# interposer.net
KiCad netlist of a schematic drawn in Altium Designer
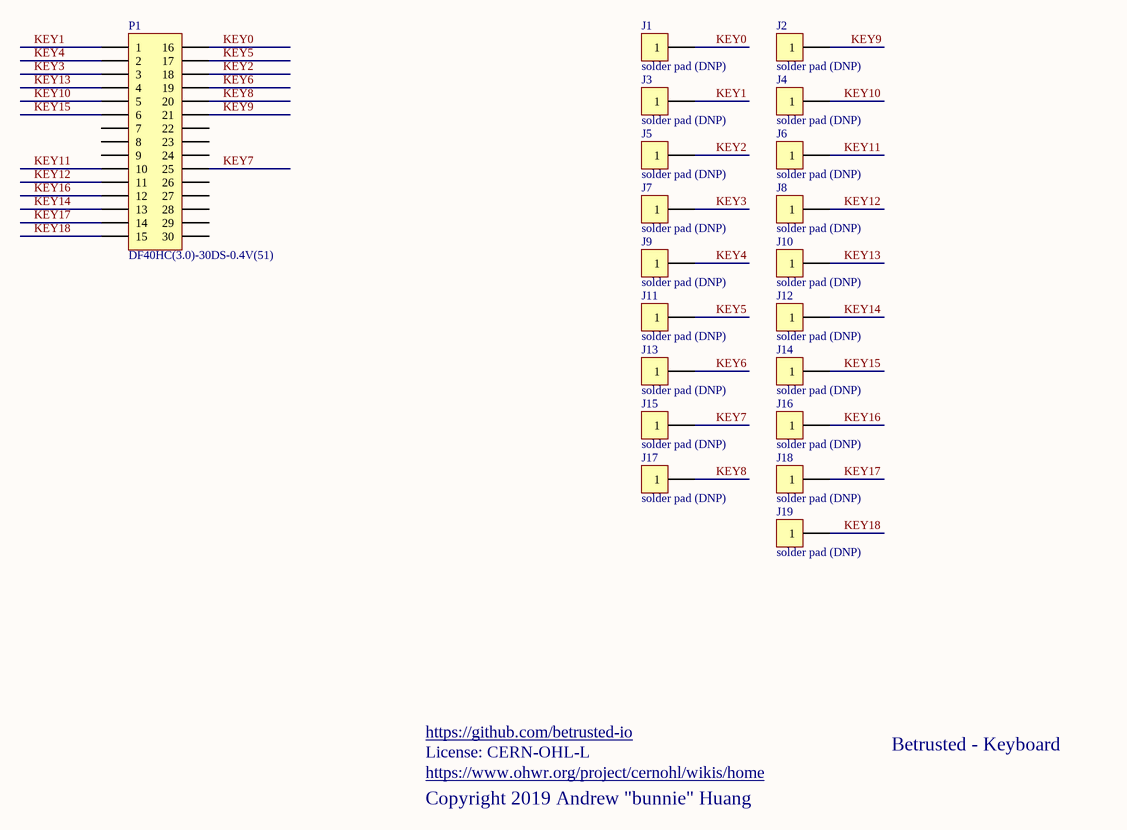
[diagram p0: interposer.SchDoc]

(export (version "E")
  (design (tool "Eeschema 10.0.6"))
  (components
    (comp (ref "J1")
      (value "solder pad (DNP)")
      (footprint "TP_TH1.0mm_1.5x2mm_SQ")
      (description "Connector")
      (fields (field (name "MPN") "DNP"))
      (libsource (lib "*") (part "CON1"))
    )
    (comp (ref "J2")
      (value "solder pad (DNP)")
      (footprint "TP_TH1.0mm_1.5x2mm_SQ")
      (description "Connector")
      (fields (field (name "MPN") "DNP"))
      (libsource (lib "*") (part "CON1"))
    )
    (comp (ref "J3")
      (value "solder pad (DNP)")
      (footprint "TP_TH1.0mm_1.5x2mm_SQ")
      (description "Connector")
      (fields (field (name "MPN") "DNP"))
      (libsource (lib "*") (part "CON1"))
    )
    (comp (ref "J4")
      (value "solder pad (DNP)")
      (footprint "TP_TH1.0mm_1.5x2mm_SQ")
      (description "Connector")
      (fields (field (name "MPN") "DNP"))
      (libsource (lib "*") (part "CON1"))
    )
    (comp (ref "J5")
      (value "solder pad (DNP)")
      (footprint "TP_TH1.0mm_1.5x2mm_SQ")
      (description "Connector")
      (fields (field (name "MPN") "DNP"))
      (libsource (lib "*") (part "CON1"))
    )
    (comp (ref "J6")
      (value "solder pad (DNP)")
      (footprint "TP_TH1.0mm_1.5x2mm_SQ")
      (description "Connector")
      (fields (field (name "MPN") "DNP"))
      (libsource (lib "*") (part "CON1"))
    )
    (comp (ref "J7")
      (value "solder pad (DNP)")
      (footprint "TP_TH1.0mm_1.5x2mm_SQ")
      (description "Connector")
      (fields (field (name "MPN") "DNP"))
      (libsource (lib "*") (part "CON1"))
    )
    (comp (ref "J8")
      (value "solder pad (DNP)")
      (footprint "TP_TH1.0mm_1.5x2mm_SQ")
      (description "Connector")
      (fields (field (name "MPN") "DNP"))
      (libsource (lib "*") (part "CON1"))
    )
    (comp (ref "J9")
      (value "solder pad (DNP)")
      (footprint "TP_TH1.0mm_1.5x2mm_SQ")
      (description "Connector")
      (fields (field (name "MPN") "DNP"))
      (libsource (lib "*") (part "CON1"))
    )
    (comp (ref "J10")
      (value "solder pad (DNP)")
      (footprint "TP_TH1.0mm_1.5x2mm_SQ")
      (description "Connector")
      (fields (field (name "MPN") "DNP"))
      (libsource (lib "*") (part "CON1"))
    )
    (comp (ref "J11")
      (value "solder pad (DNP)")
      (footprint "TP_TH1.0mm_1.5x2mm_SQ")
      (description "Connector")
      (fields (field (name "MPN") "DNP"))
      (libsource (lib "*") (part "CON1"))
    )
    (comp (ref "J12")
      (value "solder pad (DNP)")
      (footprint "TP_TH1.0mm_1.5x2mm_SQ")
      (description "Connector")
      (fields (field (name "MPN") "DNP"))
      (libsource (lib "*") (part "CON1"))
    )
    (comp (ref "J13")
      (value "solder pad (DNP)")
      (footprint "TP_TH1.0mm_1.5x2mm_SQ")
      (description "Connector")
      (fields (field (name "MPN") "DNP"))
      (libsource (lib "*") (part "CON1"))
    )
    (comp (ref "J14")
      (value "solder pad (DNP)")
      (footprint "TP_TH1.0mm_1.5x2mm_SQ")
      (description "Connector")
      (fields (field (name "MPN") "DNP"))
      (libsource (lib "*") (part "CON1"))
    )
    (comp (ref "J15")
      (value "solder pad (DNP)")
      (footprint "TP_TH1.0mm_1.5x2mm_SQ")
      (description "Connector")
      (fields (field (name "MPN") "DNP"))
      (libsource (lib "*") (part "CON1"))
    )
    (comp (ref "J16")
      (value "solder pad (DNP)")
      (footprint "TP_TH1.0mm_1.5x2mm_SQ")
      (description "Connector")
      (fields (field (name "MPN") "DNP"))
      (libsource (lib "*") (part "CON1"))
    )
    (comp (ref "J17")
      (value "solder pad (DNP)")
      (footprint "TP_TH1.0mm_1.5x2mm_SQ")
      (description "Connector")
      (fields (field (name "MPN") "DNP"))
      (libsource (lib "*") (part "CON1"))
    )
    (comp (ref "J18")
      (value "solder pad (DNP)")
      (footprint "TP_TH1.0mm_1.5x2mm_SQ")
      (description "Connector")
      (fields (field (name "MPN") "DNP"))
      (libsource (lib "*") (part "CON1"))
    )
    (comp (ref "J19")
      (value "solder pad (DNP)")
      (footprint "TP_TH1.0mm_1.5x2mm_SQ")
      (description "Connector")
      (fields (field (name "MPN") "DNP"))
      (libsource (lib "*") (part "CON1"))
    )
    (comp (ref "P1")
      (value "DF40HC(3.0)-30DS-0.4V(51)")
      (footprint "HRS_DF40HC(3.0)-30DS-0.4V(51)")
      (description "Header, 15-Pin, Dual row")
      (fields (field (name "PUBLISHER") "Altium Limited"))
      (libsource (lib "Miscellaneous Connectors") (part "Header 15X2A"))
    )
  )
  (nets
    (net (code "1") (name "/KEY0") (class "Default")
      (node (ref "J1") (pin "1") (pinfunction "1_1") (pintype "passive"))
      (node (ref "P1") (pin "16") (pinfunction "16_16") (pintype "passive"))
    )
    (net (code "2") (name "/KEY1") (class "Default")
      (node (ref "J3") (pin "1") (pinfunction "1_1") (pintype "passive"))
      (node (ref "P1") (pin "1") (pinfunction "1_1") (pintype "passive"))
    )
    (net (code "3") (name "/KEY2") (class "Default")
      (node (ref "J5") (pin "1") (pinfunction "1_1") (pintype "passive"))
      (node (ref "P1") (pin "18") (pinfunction "18_18") (pintype "passive"))
    )
    (net (code "4") (name "/KEY3") (class "Default")
      (node (ref "J7") (pin "1") (pinfunction "1_1") (pintype "passive"))
      (node (ref "P1") (pin "3") (pinfunction "3_3") (pintype "passive"))
    )
    (net (code "5") (name "/KEY4") (class "Default")
      (node (ref "J9") (pin "1") (pinfunction "1_1") (pintype "passive"))
      (node (ref "P1") (pin "2") (pinfunction "2_2") (pintype "passive"))
    )
    (net (code "6") (name "/KEY5") (class "Default")
      (node (ref "J11") (pin "1") (pinfunction "1_1") (pintype "passive"))
      (node (ref "P1") (pin "17") (pinfunction "17_17") (pintype "passive"))
    )
    (net (code "7") (name "/KEY6") (class "Default")
      (node (ref "J13") (pin "1") (pinfunction "1_1") (pintype "passive"))
      (node (ref "P1") (pin "19") (pinfunction "19_19") (pintype "passive"))
    )
    (net (code "8") (name "/KEY7") (class "Default")
      (node (ref "J15") (pin "1") (pinfunction "1_1") (pintype "passive"))
      (node (ref "P1") (pin "25") (pinfunction "25_25") (pintype "passive"))
    )
    (net (code "9") (name "/KEY8") (class "Default")
      (node (ref "J17") (pin "1") (pinfunction "1_1") (pintype "passive"))
      (node (ref "P1") (pin "20") (pinfunction "20_20") (pintype "passive"))
    )
    (net (code "10") (name "/KEY9") (class "Default")
      (node (ref "J2") (pin "1") (pinfunction "1_1") (pintype "passive"))
      (node (ref "P1") (pin "21") (pinfunction "21_21") (pintype "passive"))
    )
    (net (code "11") (name "/KEY10") (class "Default")
      (node (ref "J4") (pin "1") (pinfunction "1_1") (pintype "passive"))
      (node (ref "P1") (pin "5") (pinfunction "5_5") (pintype "passive"))
    )
    (net (code "12") (name "/KEY11") (class "Default")
      (node (ref "J6") (pin "1") (pinfunction "1_1") (pintype "passive"))
      (node (ref "P1") (pin "10") (pinfunction "10_10") (pintype "passive"))
    )
    (net (code "13") (name "/KEY12") (class "Default")
      (node (ref "J8") (pin "1") (pinfunction "1_1") (pintype "passive"))
      (node (ref "P1") (pin "11") (pinfunction "11_11") (pintype "passive"))
    )
    (net (code "14") (name "/KEY13") (class "Default")
      (node (ref "J10") (pin "1") (pinfunction "1_1") (pintype "passive"))
      (node (ref "P1") (pin "4") (pinfunction "4_4") (pintype "passive"))
    )
    (net (code "15") (name "/KEY14") (class "Default")
      (node (ref "J12") (pin "1") (pinfunction "1_1") (pintype "passive"))
      (node (ref "P1") (pin "13") (pinfunction "13_13") (pintype "passive"))
    )
    (net (code "16") (name "/KEY15") (class "Default")
      (node (ref "J14") (pin "1") (pinfunction "1_1") (pintype "passive"))
      (node (ref "P1") (pin "6") (pinfunction "6_6") (pintype "passive"))
    )
    (net (code "17") (name "/KEY16") (class "Default")
      (node (ref "J16") (pin "1") (pinfunction "1_1") (pintype "passive"))
      (node (ref "P1") (pin "12") (pinfunction "12_12") (pintype "passive"))
    )
    (net (code "18") (name "/KEY17") (class "Default")
      (node (ref "J18") (pin "1") (pinfunction "1_1") (pintype "passive"))
      (node (ref "P1") (pin "14") (pinfunction "14_14") (pintype "passive"))
    )
    (net (code "19") (name "/KEY18") (class "Default")
      (node (ref "J19") (pin "1") (pinfunction "1_1") (pintype "passive"))
      (node (ref "P1") (pin "15") (pinfunction "15_15") (pintype "passive"))
    )
    (net (code "20") (name "unconnected-(P1-Pad7)") (class "Default")
      (node (ref "P1") (pin "7") (pinfunction "7_7") (pintype "passive"))
    )
    (net (code "21") (name "unconnected-(P1-Pad8)") (class "Default")
      (node (ref "P1") (pin "8") (pinfunction "8_8") (pintype "passive"))
    )
    (net (code "22") (name "unconnected-(P1-Pad9)") (class "Default")
      (node (ref "P1") (pin "9") (pinfunction "9_9") (pintype "passive"))
    )
    (net (code "23") (name "unconnected-(P1-Pad22)") (class "Default")
      (node (ref "P1") (pin "22") (pinfunction "22_22") (pintype "passive"))
    )
    (net (code "24") (name "unconnected-(P1-Pad23)") (class "Default")
      (node (ref "P1") (pin "23") (pinfunction "23_23") (pintype "passive"))
    )
    (net (code "25") (name "unconnected-(P1-Pad24)") (class "Default")
      (node (ref "P1") (pin "24") (pinfunction "24_24") (pintype "passive"))
    )
    (net (code "26") (name "unconnected-(P1-Pad26)") (class "Default")
      (node (ref "P1") (pin "26") (pinfunction "26_26") (pintype "passive"))
    )
    (net (code "27") (name "unconnected-(P1-Pad27)") (class "Default")
      (node (ref "P1") (pin "27") (pinfunction "27_27") (pintype "passive"))
    )
    (net (code "28") (name "unconnected-(P1-Pad28)") (class "Default")
      (node (ref "P1") (pin "28") (pinfunction "28_28") (pintype "passive"))
    )
    (net (code "29") (name "unconnected-(P1-Pad29)") (class "Default")
      (node (ref "P1") (pin "29") (pinfunction "29_29") (pintype "passive"))
    )
    (net (code "30") (name "unconnected-(P1-Pad30)") (class "Default")
      (node (ref "P1") (pin "30") (pinfunction "30_30") (pintype "passive"))
    )
  )
)
